# Sheet1.net
KiCad netlist of a schematic drawn in Altium Designer
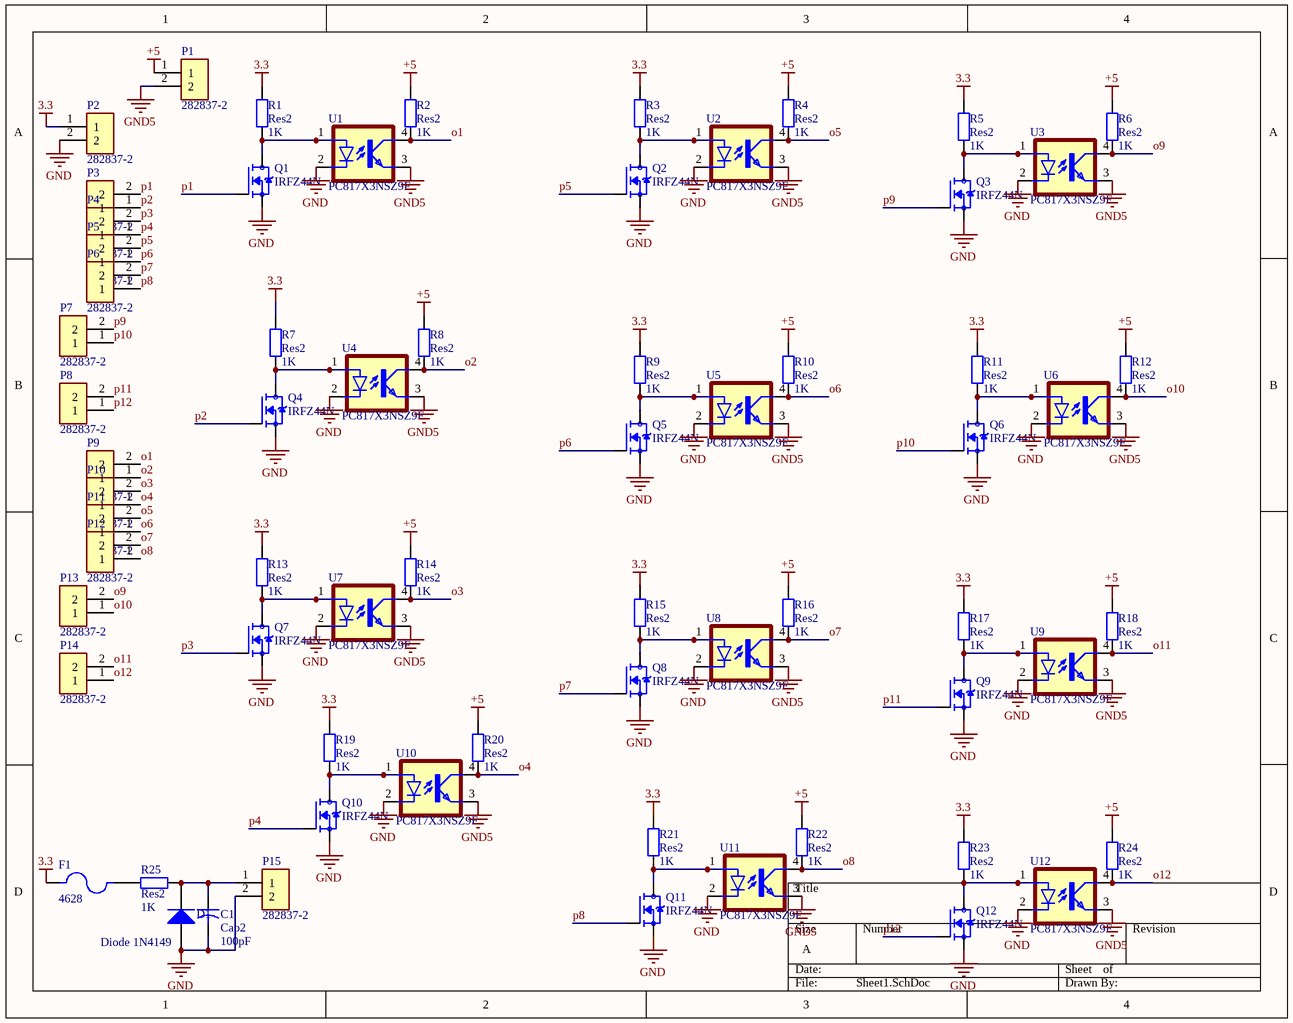
[diagram p0: Sheet1.SchDoc]

(export (version "E")
  (design (tool "Eeschema 10.0.6"))
  (components
    (comp (ref "C1")
      (value "Cap2")
      (footprint "CAPR5-4X5")
      (description "Capacitor")
      (fields (field (name "ALTIUM_VALUE") "100pF") (field (name "PUBLISHER") "Altium Limited"))
      (libsource (lib "Miscellaneous Devices") (part "Cap2"))
    )
    (comp (ref "D1")
      (value "Diode 1N4149")
      (footprint "DO-35A")
      (description "Computer Diode")
      (fields (field (name "PUBLISHER") "Altium Limited"))
      (libsource (lib "Miscellaneous Devices") (part "Diode 1N4149"))
    )
    (comp (ref "F1")
      (value "4628")
      (footprint "FUSE_4628")
      (description "5mm Slim Line Fuse holder")
      (fields (field (name "MF") "Keystone"))
      (libsource (lib "4628") (part "4628"))
    )
    (comp (ref "P1")
      (value "282837-2")
      (footprint "TE_282837-2")
      (fields (field (name "MF") "TE Connectivity"))
      (libsource (lib "") (part "282837-2_1"))
    )
    (comp (ref "P2")
      (value "282837-2")
      (footprint "TE_282837-2")
      (fields (field (name "MF") "TE Connectivity"))
      (libsource (lib "") (part "282837-2_1"))
    )
    (comp (ref "P3")
      (value "282837-2")
      (footprint "TE_282837-2")
      (fields (field (name "MF") "TE Connectivity"))
      (libsource (lib "282837-2") (part "282837-2"))
    )
    (comp (ref "P4")
      (value "282837-2")
      (footprint "TE_282837-2")
      (fields (field (name "MF") "TE Connectivity"))
      (libsource (lib "282837-2") (part "282837-2"))
    )
    (comp (ref "P5")
      (value "282837-2")
      (footprint "TE_282837-2")
      (fields (field (name "MF") "TE Connectivity"))
      (libsource (lib "282837-2") (part "282837-2"))
    )
    (comp (ref "P6")
      (value "282837-2")
      (footprint "TE_282837-2")
      (fields (field (name "MF") "TE Connectivity"))
      (libsource (lib "282837-2") (part "282837-2"))
    )
    (comp (ref "P7")
      (value "282837-2")
      (footprint "TE_282837-2")
      (fields (field (name "MF") "TE Connectivity"))
      (libsource (lib "282837-2") (part "282837-2"))
    )
    (comp (ref "P8")
      (value "282837-2")
      (footprint "TE_282837-2")
      (fields (field (name "MF") "TE Connectivity"))
      (libsource (lib "282837-2") (part "282837-2"))
    )
    (comp (ref "P9")
      (value "282837-2")
      (footprint "TE_282837-2")
      (fields (field (name "MF") "TE Connectivity"))
      (libsource (lib "282837-2") (part "282837-2"))
    )
    (comp (ref "P10")
      (value "282837-2")
      (footprint "TE_282837-2")
      (fields (field (name "MF") "TE Connectivity"))
      (libsource (lib "282837-2") (part "282837-2"))
    )
    (comp (ref "P11")
      (value "282837-2")
      (footprint "TE_282837-2")
      (fields (field (name "MF") "TE Connectivity"))
      (libsource (lib "282837-2") (part "282837-2"))
    )
    (comp (ref "P12")
      (value "282837-2")
      (footprint "TE_282837-2")
      (fields (field (name "MF") "TE Connectivity"))
      (libsource (lib "282837-2") (part "282837-2"))
    )
    (comp (ref "P13")
      (value "282837-2")
      (footprint "TE_282837-2")
      (fields (field (name "MF") "TE Connectivity"))
      (libsource (lib "282837-2") (part "282837-2"))
    )
    (comp (ref "P14")
      (value "282837-2")
      (footprint "TE_282837-2")
      (fields (field (name "MF") "TE Connectivity"))
      (libsource (lib "282837-2") (part "282837-2"))
    )
    (comp (ref "P15")
      (value "282837-2")
      (footprint "TE_282837-2")
      (fields (field (name "MF") "TE Connectivity"))
      (libsource (lib "") (part "282837-2_1"))
    )
    (comp (ref "Q1")
      (value "IRFZ44N")
      (footprint "TO254P1016X419X2286-3")
      (description "N-Channel 55 V 49A (Tc) 94W (Tc) Through Hole TO-220AB")
      (fields (field (name "MF") "Infineon Technologies"))
      (libsource (lib "IRFZ44N") (part "IRFZ44N"))
    )
    (comp (ref "Q2")
      (value "IRFZ44N")
      (footprint "TO254P1016X419X2286-3")
      (description "N-Channel 55 V 49A (Tc) 94W (Tc) Through Hole TO-220AB")
      (fields (field (name "MF") "Infineon Technologies"))
      (libsource (lib "IRFZ44N") (part "IRFZ44N"))
    )
    (comp (ref "Q3")
      (value "IRFZ44N")
      (footprint "TO254P1016X419X2286-3")
      (description "N-Channel 55 V 49A (Tc) 94W (Tc) Through Hole TO-220AB")
      (fields (field (name "MF") "Infineon Technologies"))
      (libsource (lib "IRFZ44N") (part "IRFZ44N"))
    )
    (comp (ref "Q4")
      (value "IRFZ44N")
      (footprint "TO254P1016X419X2286-3")
      (description "N-Channel 55 V 49A (Tc) 94W (Tc) Through Hole TO-220AB")
      (fields (field (name "MF") "Infineon Technologies"))
      (libsource (lib "IRFZ44N") (part "IRFZ44N"))
    )
    (comp (ref "Q5")
      (value "IRFZ44N")
      (footprint "TO254P1016X419X2286-3")
      (description "N-Channel 55 V 49A (Tc) 94W (Tc) Through Hole TO-220AB")
      (fields (field (name "MF") "Infineon Technologies"))
      (libsource (lib "IRFZ44N") (part "IRFZ44N"))
    )
    (comp (ref "Q6")
      (value "IRFZ44N")
      (footprint "TO254P1016X419X2286-3")
      (description "N-Channel 55 V 49A (Tc) 94W (Tc) Through Hole TO-220AB")
      (fields (field (name "MF") "Infineon Technologies"))
      (libsource (lib "IRFZ44N") (part "IRFZ44N"))
    )
    (comp (ref "Q7")
      (value "IRFZ44N")
      (footprint "TO254P1016X419X2286-3")
      (description "N-Channel 55 V 49A (Tc) 94W (Tc) Through Hole TO-220AB")
      (fields (field (name "MF") "Infineon Technologies"))
      (libsource (lib "IRFZ44N") (part "IRFZ44N"))
    )
    (comp (ref "Q8")
      (value "IRFZ44N")
      (footprint "TO254P1016X419X2286-3")
      (description "N-Channel 55 V 49A (Tc) 94W (Tc) Through Hole TO-220AB")
      (fields (field (name "MF") "Infineon Technologies"))
      (libsource (lib "IRFZ44N") (part "IRFZ44N"))
    )
    (comp (ref "Q9")
      (value "IRFZ44N")
      (footprint "TO254P1016X419X2286-3")
      (description "N-Channel 55 V 49A (Tc) 94W (Tc) Through Hole TO-220AB")
      (fields (field (name "MF") "Infineon Technologies"))
      (libsource (lib "IRFZ44N") (part "IRFZ44N"))
    )
    (comp (ref "Q10")
      (value "IRFZ44N")
      (footprint "TO254P1016X419X2286-3")
      (description "N-Channel 55 V 49A (Tc) 94W (Tc) Through Hole TO-220AB")
      (fields (field (name "MF") "Infineon Technologies"))
      (libsource (lib "IRFZ44N") (part "IRFZ44N"))
    )
    (comp (ref "Q11")
      (value "IRFZ44N")
      (footprint "TO254P1016X419X2286-3")
      (description "N-Channel 55 V 49A (Tc) 94W (Tc) Through Hole TO-220AB")
      (fields (field (name "MF") "Infineon Technologies"))
      (libsource (lib "IRFZ44N") (part "IRFZ44N"))
    )
    (comp (ref "Q12")
      (value "IRFZ44N")
      (footprint "TO254P1016X419X2286-3")
      (description "N-Channel 55 V 49A (Tc) 94W (Tc) Through Hole TO-220AB")
      (fields (field (name "MF") "Infineon Technologies"))
      (libsource (lib "IRFZ44N") (part "IRFZ44N"))
    )
    (comp (ref "R1")
      (value "Res2")
      (footprint "AXIAL-0.4")
      (description "Resistor")
      (fields (field (name "ALTIUM_VALUE") "1K") (field (name "PUBLISHER") "Altium Limited"))
      (libsource (lib "Miscellaneous Devices") (part "Res2"))
    )
    (comp (ref "R2")
      (value "Res2")
      (footprint "AXIAL-0.4")
      (description "Resistor")
      (fields (field (name "ALTIUM_VALUE") "1K") (field (name "PUBLISHER") "Altium Limited"))
      (libsource (lib "Miscellaneous Devices") (part "Res2"))
    )
    (comp (ref "R3")
      (value "Res2")
      (footprint "AXIAL-0.4")
      (description "Resistor")
      (fields (field (name "ALTIUM_VALUE") "1K") (field (name "PUBLISHER") "Altium Limited"))
      (libsource (lib "Miscellaneous Devices") (part "Res2"))
    )
    (comp (ref "R4")
      (value "Res2")
      (footprint "AXIAL-0.4")
      (description "Resistor")
      (fields (field (name "ALTIUM_VALUE") "1K") (field (name "PUBLISHER") "Altium Limited"))
      (libsource (lib "Miscellaneous Devices") (part "Res2"))
    )
    (comp (ref "R5")
      (value "Res2")
      (footprint "AXIAL-0.4")
      (description "Resistor")
      (fields (field (name "ALTIUM_VALUE") "1K") (field (name "PUBLISHER") "Altium Limited"))
      (libsource (lib "Miscellaneous Devices") (part "Res2"))
    )
    (comp (ref "R6")
      (value "Res2")
      (footprint "AXIAL-0.4")
      (description "Resistor")
      (fields (field (name "ALTIUM_VALUE") "1K") (field (name "PUBLISHER") "Altium Limited"))
      (libsource (lib "Miscellaneous Devices") (part "Res2"))
    )
    (comp (ref "R7")
      (value "Res2")
      (footprint "AXIAL-0.4")
      (description "Resistor")
      (fields (field (name "ALTIUM_VALUE") "1K") (field (name "PUBLISHER") "Altium Limited"))
      (libsource (lib "Miscellaneous Devices") (part "Res2"))
    )
    (comp (ref "R8")
      (value "Res2")
      (footprint "AXIAL-0.4")
      (description "Resistor")
      (fields (field (name "ALTIUM_VALUE") "1K") (field (name "PUBLISHER") "Altium Limited"))
      (libsource (lib "Miscellaneous Devices") (part "Res2"))
    )
    (comp (ref "R9")
      (value "Res2")
      (footprint "AXIAL-0.4")
      (description "Resistor")
      (fields (field (name "ALTIUM_VALUE") "1K") (field (name "PUBLISHER") "Altium Limited"))
      (libsource (lib "Miscellaneous Devices") (part "Res2"))
    )
    (comp (ref "R10")
      (value "Res2")
      (footprint "AXIAL-0.4")
      (description "Resistor")
      (fields (field (name "ALTIUM_VALUE") "1K") (field (name "PUBLISHER") "Altium Limited"))
      (libsource (lib "Miscellaneous Devices") (part "Res2"))
    )
    (comp (ref "R11")
      (value "Res2")
      (footprint "AXIAL-0.4")
      (description "Resistor")
      (fields (field (name "ALTIUM_VALUE") "1K") (field (name "PUBLISHER") "Altium Limited"))
      (libsource (lib "Miscellaneous Devices") (part "Res2"))
    )
    (comp (ref "R12")
      (value "Res2")
      (footprint "AXIAL-0.4")
      (description "Resistor")
      (fields (field (name "ALTIUM_VALUE") "1K") (field (name "PUBLISHER") "Altium Limited"))
      (libsource (lib "Miscellaneous Devices") (part "Res2"))
    )
    (comp (ref "R13")
      (value "Res2")
      (footprint "AXIAL-0.4")
      (description "Resistor")
      (fields (field (name "ALTIUM_VALUE") "1K") (field (name "PUBLISHER") "Altium Limited"))
      (libsource (lib "Miscellaneous Devices") (part "Res2"))
    )
    (comp (ref "R14")
      (value "Res2")
      (footprint "AXIAL-0.4")
      (description "Resistor")
      (fields (field (name "ALTIUM_VALUE") "1K") (field (name "PUBLISHER") "Altium Limited"))
      (libsource (lib "Miscellaneous Devices") (part "Res2"))
    )
    (comp (ref "R15")
      (value "Res2")
      (footprint "AXIAL-0.4")
      (description "Resistor")
      (fields (field (name "ALTIUM_VALUE") "1K") (field (name "PUBLISHER") "Altium Limited"))
      (libsource (lib "Miscellaneous Devices") (part "Res2"))
    )
    (comp (ref "R16")
      (value "Res2")
      (footprint "AXIAL-0.4")
      (description "Resistor")
      (fields (field (name "ALTIUM_VALUE") "1K") (field (name "PUBLISHER") "Altium Limited"))
      (libsource (lib "Miscellaneous Devices") (part "Res2"))
    )
    (comp (ref "R17")
      (value "Res2")
      (footprint "AXIAL-0.4")
      (description "Resistor")
      (fields (field (name "ALTIUM_VALUE") "1K") (field (name "PUBLISHER") "Altium Limited"))
      (libsource (lib "Miscellaneous Devices") (part "Res2"))
    )
    (comp (ref "R18")
      (value "Res2")
      (footprint "AXIAL-0.4")
      (description "Resistor")
      (fields (field (name "ALTIUM_VALUE") "1K") (field (name "PUBLISHER") "Altium Limited"))
      (libsource (lib "Miscellaneous Devices") (part "Res2"))
    )
    (comp (ref "R19")
      (value "Res2")
      (footprint "AXIAL-0.4")
      (description "Resistor")
      (fields (field (name "ALTIUM_VALUE") "1K") (field (name "PUBLISHER") "Altium Limited"))
      (libsource (lib "Miscellaneous Devices") (part "Res2"))
    )
    (comp (ref "R20")
      (value "Res2")
      (footprint "AXIAL-0.4")
      (description "Resistor")
      (fields (field (name "ALTIUM_VALUE") "1K") (field (name "PUBLISHER") "Altium Limited"))
      (libsource (lib "Miscellaneous Devices") (part "Res2"))
    )
    (comp (ref "R21")
      (value "Res2")
      (footprint "AXIAL-0.4")
      (description "Resistor")
      (fields (field (name "ALTIUM_VALUE") "1K") (field (name "PUBLISHER") "Altium Limited"))
      (libsource (lib "Miscellaneous Devices") (part "Res2"))
    )
    (comp (ref "R22")
      (value "Res2")
      (footprint "AXIAL-0.4")
      (description "Resistor")
      (fields (field (name "ALTIUM_VALUE") "1K") (field (name "PUBLISHER") "Altium Limited"))
      (libsource (lib "Miscellaneous Devices") (part "Res2"))
    )
    (comp (ref "R23")
      (value "Res2")
      (footprint "AXIAL-0.4")
      (description "Resistor")
      (fields (field (name "ALTIUM_VALUE") "1K") (field (name "PUBLISHER") "Altium Limited"))
      (libsource (lib "Miscellaneous Devices") (part "Res2"))
    )
    (comp (ref "R24")
      (value "Res2")
      (footprint "AXIAL-0.4")
      (description "Resistor")
      (fields (field (name "ALTIUM_VALUE") "1K") (field (name "PUBLISHER") "Altium Limited"))
      (libsource (lib "Miscellaneous Devices") (part "Res2"))
    )
    (comp (ref "R25")
      (value "Res2")
      (footprint "AXIAL-0.4")
      (description "Resistor")
      (fields (field (name "ALTIUM_VALUE") "1K") (field (name "PUBLISHER") "Altium Limited"))
      (libsource (lib "") (part "Res2_1"))
    )
    (comp (ref "U1")
      (value "PC817X3NSZ9F")
      (footprint "DIL04")
      (description "Optoisolator Transistor Output 5000Vrms 1 Channel 4-DIP")
      (fields (field (name "MF") "Sharp Microelectronics"))
      (libsource (lib "PC817X3NSZ9F") (part "PC817X3NSZ9F"))
    )
    (comp (ref "U2")
      (value "PC817X3NSZ9F")
      (footprint "DIL04")
      (description "Optoisolator Transistor Output 5000Vrms 1 Channel 4-DIP")
      (fields (field (name "MF") "Sharp Microelectronics"))
      (libsource (lib "PC817X3NSZ9F") (part "PC817X3NSZ9F"))
    )
    (comp (ref "U3")
      (value "PC817X3NSZ9F")
      (footprint "DIL04")
      (description "Optoisolator Transistor Output 5000Vrms 1 Channel 4-DIP")
      (fields (field (name "MF") "Sharp Microelectronics"))
      (libsource (lib "PC817X3NSZ9F") (part "PC817X3NSZ9F"))
    )
    (comp (ref "U4")
      (value "PC817X3NSZ9F")
      (footprint "DIL04")
      (description "Optoisolator Transistor Output 5000Vrms 1 Channel 4-DIP")
      (fields (field (name "MF") "Sharp Microelectronics"))
      (libsource (lib "PC817X3NSZ9F") (part "PC817X3NSZ9F"))
    )
    (comp (ref "U5")
      (value "PC817X3NSZ9F")
      (footprint "DIL04")
      (description "Optoisolator Transistor Output 5000Vrms 1 Channel 4-DIP")
      (fields (field (name "MF") "Sharp Microelectronics"))
      (libsource (lib "PC817X3NSZ9F") (part "PC817X3NSZ9F"))
    )
    (comp (ref "U6")
      (value "PC817X3NSZ9F")
      (footprint "DIL04")
      (description "Optoisolator Transistor Output 5000Vrms 1 Channel 4-DIP")
      (fields (field (name "MF") "Sharp Microelectronics"))
      (libsource (lib "PC817X3NSZ9F") (part "PC817X3NSZ9F"))
    )
    (comp (ref "U7")
      (value "PC817X3NSZ9F")
      (footprint "DIL04")
      (description "Optoisolator Transistor Output 5000Vrms 1 Channel 4-DIP")
      (fields (field (name "MF") "Sharp Microelectronics"))
      (libsource (lib "PC817X3NSZ9F") (part "PC817X3NSZ9F"))
    )
    (comp (ref "U8")
      (value "PC817X3NSZ9F")
      (footprint "DIL04")
      (description "Optoisolator Transistor Output 5000Vrms 1 Channel 4-DIP")
      (fields (field (name "MF") "Sharp Microelectronics"))
      (libsource (lib "PC817X3NSZ9F") (part "PC817X3NSZ9F"))
    )
    (comp (ref "U9")
      (value "PC817X3NSZ9F")
      (footprint "DIL04")
      (description "Optoisolator Transistor Output 5000Vrms 1 Channel 4-DIP")
      (fields (field (name "MF") "Sharp Microelectronics"))
      (libsource (lib "PC817X3NSZ9F") (part "PC817X3NSZ9F"))
    )
    (comp (ref "U10")
      (value "PC817X3NSZ9F")
      (footprint "DIL04")
      (description "Optoisolator Transistor Output 5000Vrms 1 Channel 4-DIP")
      (fields (field (name "MF") "Sharp Microelectronics"))
      (libsource (lib "PC817X3NSZ9F") (part "PC817X3NSZ9F"))
    )
    (comp (ref "U11")
      (value "PC817X3NSZ9F")
      (footprint "DIL04")
      (description "Optoisolator Transistor Output 5000Vrms 1 Channel 4-DIP")
      (fields (field (name "MF") "Sharp Microelectronics"))
      (libsource (lib "PC817X3NSZ9F") (part "PC817X3NSZ9F"))
    )
    (comp (ref "U12")
      (value "PC817X3NSZ9F")
      (footprint "DIL04")
      (description "Optoisolator Transistor Output 5000Vrms 1 Channel 4-DIP")
      (fields (field (name "MF") "Sharp Microelectronics"))
      (libsource (lib "PC817X3NSZ9F") (part "PC817X3NSZ9F"))
    )
  )
  (nets
    (net (code "1") (name "+5") (class "Default")
      (node (ref "P1") (pin "1") (pinfunction "1_1") (pintype "passive"))
      (node (ref "R10") (pin "2") (pinfunction "2_2") (pintype "passive"))
      (node (ref "R12") (pin "2") (pinfunction "2_2") (pintype "passive"))
      (node (ref "R14") (pin "2") (pinfunction "2_2") (pintype "passive"))
      (node (ref "R16") (pin "2") (pinfunction "2_2") (pintype "passive"))
      (node (ref "R18") (pin "2") (pinfunction "2_2") (pintype "passive"))
      (node (ref "R2") (pin "2") (pinfunction "2_2") (pintype "passive"))
      (node (ref "R20") (pin "2") (pinfunction "2_2") (pintype "passive"))
      (node (ref "R22") (pin "2") (pinfunction "2_2") (pintype "passive"))
      (node (ref "R24") (pin "2") (pinfunction "2_2") (pintype "passive"))
      (node (ref "R4") (pin "2") (pinfunction "2_2") (pintype "passive"))
      (node (ref "R6") (pin "2") (pinfunction "2_2") (pintype "passive"))
      (node (ref "R8") (pin "2") (pinfunction "2_2") (pintype "passive"))
    )
    (net (code "2") (name "/o1") (class "Default")
      (node (ref "P9") (pin "2") (pinfunction "2_2") (pintype "passive"))
      (node (ref "R2") (pin "1") (pinfunction "1_1") (pintype "passive"))
      (node (ref "U1") (pin "4") (pinfunction "COL_4") (pintype "passive"))
    )
    (net (code "3") (name "/o2") (class "Default")
      (node (ref "P9") (pin "1") (pinfunction "1_1") (pintype "passive"))
      (node (ref "R8") (pin "1") (pinfunction "1_1") (pintype "passive"))
      (node (ref "U4") (pin "4") (pinfunction "COL_4") (pintype "passive"))
    )
    (net (code "4") (name "/o3") (class "Default")
      (node (ref "P10") (pin "2") (pinfunction "2_2") (pintype "passive"))
      (node (ref "R14") (pin "1") (pinfunction "1_1") (pintype "passive"))
      (node (ref "U7") (pin "4") (pinfunction "COL_4") (pintype "passive"))
    )
    (net (code "5") (name "/o4") (class "Default")
      (node (ref "P10") (pin "1") (pinfunction "1_1") (pintype "passive"))
      (node (ref "R20") (pin "1") (pinfunction "1_1") (pintype "passive"))
      (node (ref "U10") (pin "4") (pinfunction "COL_4") (pintype "passive"))
    )
    (net (code "6") (name "/o5") (class "Default")
      (node (ref "P11") (pin "2") (pinfunction "2_2") (pintype "passive"))
      (node (ref "R4") (pin "1") (pinfunction "1_1") (pintype "passive"))
      (node (ref "U2") (pin "4") (pinfunction "COL_4") (pintype "passive"))
    )
    (net (code "7") (name "/o6") (class "Default")
      (node (ref "P11") (pin "1") (pinfunction "1_1") (pintype "passive"))
      (node (ref "R10") (pin "1") (pinfunction "1_1") (pintype "passive"))
      (node (ref "U5") (pin "4") (pinfunction "COL_4") (pintype "passive"))
    )
    (net (code "8") (name "/o7") (class "Default")
      (node (ref "P12") (pin "2") (pinfunction "2_2") (pintype "passive"))
      (node (ref "R16") (pin "1") (pinfunction "1_1") (pintype "passive"))
      (node (ref "U8") (pin "4") (pinfunction "COL_4") (pintype "passive"))
    )
    (net (code "9") (name "/o8") (class "Default")
      (node (ref "P12") (pin "1") (pinfunction "1_1") (pintype "passive"))
      (node (ref "R22") (pin "1") (pinfunction "1_1") (pintype "passive"))
      (node (ref "U11") (pin "4") (pinfunction "COL_4") (pintype "passive"))
    )
    (net (code "10") (name "/o9") (class "Default")
      (node (ref "P13") (pin "2") (pinfunction "2_2") (pintype "passive"))
      (node (ref "R6") (pin "1") (pinfunction "1_1") (pintype "passive"))
      (node (ref "U3") (pin "4") (pinfunction "COL_4") (pintype "passive"))
    )
    (net (code "11") (name "/o10") (class "Default")
      (node (ref "P13") (pin "1") (pinfunction "1_1") (pintype "passive"))
      (node (ref "R12") (pin "1") (pinfunction "1_1") (pintype "passive"))
      (node (ref "U6") (pin "4") (pinfunction "COL_4") (pintype "passive"))
    )
    (net (code "12") (name "/o11") (class "Default")
      (node (ref "P14") (pin "2") (pinfunction "2_2") (pintype "passive"))
      (node (ref "R18") (pin "1") (pinfunction "1_1") (pintype "passive"))
      (node (ref "U9") (pin "4") (pinfunction "COL_4") (pintype "passive"))
    )
    (net (code "13") (name "/o12") (class "Default")
      (node (ref "P14") (pin "1") (pinfunction "1_1") (pintype "passive"))
      (node (ref "R24") (pin "1") (pinfunction "1_1") (pintype "passive"))
      (node (ref "U12") (pin "4") (pinfunction "COL_4") (pintype "passive"))
    )
    (net (code "14") (name "/p1") (class "Default")
      (node (ref "P3") (pin "2") (pinfunction "2_2") (pintype "passive"))
      (node (ref "Q1") (pin "1") (pinfunction "G_1") (pintype "passive"))
    )
    (net (code "15") (name "/p2") (class "Default")
      (node (ref "P3") (pin "1") (pinfunction "1_1") (pintype "passive"))
      (node (ref "Q4") (pin "1") (pinfunction "G_1") (pintype "passive"))
    )
    (net (code "16") (name "/p3") (class "Default")
      (node (ref "P4") (pin "2") (pinfunction "2_2") (pintype "passive"))
      (node (ref "Q7") (pin "1") (pinfunction "G_1") (pintype "passive"))
    )
    (net (code "17") (name "/p4") (class "Default")
      (node (ref "P4") (pin "1") (pinfunction "1_1") (pintype "passive"))
      (node (ref "Q10") (pin "1") (pinfunction "G_1") (pintype "passive"))
    )
    (net (code "18") (name "/p5") (class "Default")
      (node (ref "P5") (pin "2") (pinfunction "2_2") (pintype "passive"))
      (node (ref "Q2") (pin "1") (pinfunction "G_1") (pintype "passive"))
    )
    (net (code "19") (name "/p6") (class "Default")
      (node (ref "P5") (pin "1") (pinfunction "1_1") (pintype "passive"))
      (node (ref "Q5") (pin "1") (pinfunction "G_1") (pintype "passive"))
    )
    (net (code "20") (name "/p7") (class "Default")
      (node (ref "P6") (pin "2") (pinfunction "2_2") (pintype "passive"))
      (node (ref "Q8") (pin "1") (pinfunction "G_1") (pintype "passive"))
    )
    (net (code "21") (name "/p8") (class "Default")
      (node (ref "P6") (pin "1") (pinfunction "1_1") (pintype "passive"))
      (node (ref "Q11") (pin "1") (pinfunction "G_1") (pintype "passive"))
    )
    (net (code "22") (name "/p9") (class "Default")
      (node (ref "P7") (pin "2") (pinfunction "2_2") (pintype "passive"))
      (node (ref "Q3") (pin "1") (pinfunction "G_1") (pintype "passive"))
    )
    (net (code "23") (name "/p10") (class "Default")
      (node (ref "P7") (pin "1") (pinfunction "1_1") (pintype "passive"))
      (node (ref "Q6") (pin "1") (pinfunction "G_1") (pintype "passive"))
    )
    (net (code "24") (name "/p11") (class "Default")
      (node (ref "P8") (pin "2") (pinfunction "2_2") (pintype "passive"))
      (node (ref "Q9") (pin "1") (pinfunction "G_1") (pintype "passive"))
    )
    (net (code "25") (name "/p12") (class "Default")
      (node (ref "P8") (pin "1") (pinfunction "1_1") (pintype "passive"))
      (node (ref "Q12") (pin "1") (pinfunction "G_1") (pintype "passive"))
    )
    (net (code "26") (name "3.3") (class "Default")
      (node (ref "F1") (pin "1") (pinfunction "1_1") (pintype "passive"))
      (node (ref "P2") (pin "1") (pinfunction "1_1") (pintype "passive"))
      (node (ref "R1") (pin "2") (pinfunction "2_2") (pintype "passive"))
      (node (ref "R11") (pin "2") (pinfunction "2_2") (pintype "passive"))
      (node (ref "R13") (pin "2") (pinfunction "2_2") (pintype "passive"))
      (node (ref "R15") (pin "2") (pinfunction "2_2") (pintype "passive"))
      (node (ref "R17") (pin "2") (pinfunction "2_2") (pintype "passive"))
      (node (ref "R19") (pin "2") (pinfunction "2_2") (pintype "passive"))
      (node (ref "R21") (pin "2") (pinfunction "2_2") (pintype "passive"))
      (node (ref "R23") (pin "2") (pinfunction "2_2") (pintype "passive"))
      (node (ref "R3") (pin "2") (pinfunction "2_2") (pintype "passive"))
      (node (ref "R5") (pin "2") (pinfunction "2_2") (pintype "passive"))
      (node (ref "R7") (pin "2") (pinfunction "2_2") (pintype "passive"))
      (node (ref "R9") (pin "2") (pinfunction "2_2") (pintype "passive"))
    )
    (net (code "27") (name "GND") (class "Default")
      (node (ref "C1") (pin "2") (pinfunction "2_2") (pintype "passive"))
      (node (ref "D1") (pin "1") (pinfunction "A_1") (pintype "passive"))
      (node (ref "P15") (pin "2") (pinfunction "2_2") (pintype "passive"))
      (node (ref "P2") (pin "2") (pinfunction "2_2") (pintype "passive"))
      (node (ref "Q1") (pin "3") (pinfunction "S_3") (pintype "passive"))
      (node (ref "Q10") (pin "3") (pinfunction "S_3") (pintype "passive"))
      (node (ref "Q11") (pin "3") (pinfunction "S_3") (pintype "passive"))
      (node (ref "Q12") (pin "3") (pinfunction "S_3") (pintype "passive"))
      (node (ref "Q2") (pin "3") (pinfunction "S_3") (pintype "passive"))
      (node (ref "Q3") (pin "3") (pinfunction "S_3") (pintype "passive"))
      (node (ref "Q4") (pin "3") (pinfunction "S_3") (pintype "passive"))
      (node (ref "Q5") (pin "3") (pinfunction "S_3") (pintype "passive"))
      (node (ref "Q6") (pin "3") (pinfunction "S_3") (pintype "passive"))
      (node (ref "Q7") (pin "3") (pinfunction "S_3") (pintype "passive"))
      (node (ref "Q8") (pin "3") (pinfunction "S_3") (pintype "passive"))
      (node (ref "Q9") (pin "3") (pinfunction "S_3") (pintype "passive"))
      (node (ref "U1") (pin "2") (pinfunction "C_2") (pintype "passive"))
      (node (ref "U10") (pin "2") (pinfunction "C_2") (pintype "passive"))
      (node (ref "U11") (pin "2") (pinfunction "C_2") (pintype "passive"))
      (node (ref "U12") (pin "2") (pinfunction "C_2") (pintype "passive"))
      (node (ref "U2") (pin "2") (pinfunction "C_2") (pintype "passive"))
      (node (ref "U3") (pin "2") (pinfunction "C_2") (pintype "passive"))
      (node (ref "U4") (pin "2") (pinfunction "C_2") (pintype "passive"))
      (node (ref "U5") (pin "2") (pinfunction "C_2") (pintype "passive"))
      (node (ref "U6") (pin "2") (pinfunction "C_2") (pintype "passive"))
      (node (ref "U7") (pin "2") (pinfunction "C_2") (pintype "passive"))
      (node (ref "U8") (pin "2") (pinfunction "C_2") (pintype "passive"))
      (node (ref "U9") (pin "2") (pinfunction "C_2") (pintype "passive"))
    )
    (net (code "28") (name "GND5") (class "Default")
      (node (ref "P1") (pin "2") (pinfunction "2_2") (pintype "passive"))
      (node (ref "U1") (pin "3") (pinfunction "EMIT_3") (pintype "passive"))
      (node (ref "U10") (pin "3") (pinfunction "EMIT_3") (pintype "passive"))
      (node (ref "U11") (pin "3") (pinfunction "EMIT_3") (pintype "passive"))
      (node (ref "U12") (pin "3") (pinfunction "EMIT_3") (pintype "passive"))
      (node (ref "U2") (pin "3") (pinfunction "EMIT_3") (pintype "passive"))
      (node (ref "U3") (pin "3") (pinfunction "EMIT_3") (pintype "passive"))
      (node (ref "U4") (pin "3") (pinfunction "EMIT_3") (pintype "passive"))
      (node (ref "U5") (pin "3") (pinfunction "EMIT_3") (pintype "passive"))
      (node (ref "U6") (pin "3") (pinfunction "EMIT_3") (pintype "passive"))
      (node (ref "U7") (pin "3") (pinfunction "EMIT_3") (pintype "passive"))
      (node (ref "U8") (pin "3") (pinfunction "EMIT_3") (pintype "passive"))
      (node (ref "U9") (pin "3") (pinfunction "EMIT_3") (pintype "passive"))
    )
    (net (code "29") (name "Net-(D1-K)") (class "Default")
      (node (ref "C1") (pin "1") (pinfunction "1_1") (pintype "passive"))
      (node (ref "D1") (pin "2") (pinfunction "K_2") (pintype "passive"))
      (node (ref "P15") (pin "1") (pinfunction "1_1") (pintype "passive"))
      (node (ref "R25") (pin "1") (pinfunction "1_1") (pintype "passive"))
    )
    (net (code "30") (name "Net-(F1-Pad2)") (class "Default")
      (node (ref "F1") (pin "2") (pinfunction "2_2") (pintype "passive"))
      (node (ref "R25") (pin "2") (pinfunction "2_2") (pintype "passive"))
    )
    (net (code "31") (name "Net-(Q1-D)") (class "Default")
      (node (ref "Q1") (pin "2") (pinfunction "D_2") (pintype "passive"))
      (node (ref "R1") (pin "1") (pinfunction "1_1") (pintype "passive"))
      (node (ref "U1") (pin "1") (pinfunction "A_1") (pintype "passive"))
    )
    (net (code "32") (name "Net-(Q2-D)") (class "Default")
      (node (ref "Q2") (pin "2") (pinfunction "D_2") (pintype "passive"))
      (node (ref "R3") (pin "1") (pinfunction "1_1") (pintype "passive"))
      (node (ref "U2") (pin "1") (pinfunction "A_1") (pintype "passive"))
    )
    (net (code "33") (name "Net-(Q3-D)") (class "Default")
      (node (ref "Q3") (pin "2") (pinfunction "D_2") (pintype "passive"))
      (node (ref "R5") (pin "1") (pinfunction "1_1") (pintype "passive"))
      (node (ref "U3") (pin "1") (pinfunction "A_1") (pintype "passive"))
    )
    (net (code "34") (name "Net-(Q4-D)") (class "Default")
      (node (ref "Q4") (pin "2") (pinfunction "D_2") (pintype "passive"))
      (node (ref "R7") (pin "1") (pinfunction "1_1") (pintype "passive"))
      (node (ref "U4") (pin "1") (pinfunction "A_1") (pintype "passive"))
    )
    (net (code "35") (name "Net-(Q5-D)") (class "Default")
      (node (ref "Q5") (pin "2") (pinfunction "D_2") (pintype "passive"))
      (node (ref "R9") (pin "1") (pinfunction "1_1") (pintype "passive"))
      (node (ref "U5") (pin "1") (pinfunction "A_1") (pintype "passive"))
    )
    (net (code "36") (name "Net-(Q6-D)") (class "Default")
      (node (ref "Q6") (pin "2") (pinfunction "D_2") (pintype "passive"))
      (node (ref "R11") (pin "1") (pinfunction "1_1") (pintype "passive"))
      (node (ref "U6") (pin "1") (pinfunction "A_1") (pintype "passive"))
    )
    (net (code "37") (name "Net-(Q7-D)") (class "Default")
      (node (ref "Q7") (pin "2") (pinfunction "D_2") (pintype "passive"))
      (node (ref "R13") (pin "1") (pinfunction "1_1") (pintype "passive"))
      (node (ref "U7") (pin "1") (pinfunction "A_1") (pintype "passive"))
    )
    (net (code "38") (name "Net-(Q8-D)") (class "Default")
      (node (ref "Q8") (pin "2") (pinfunction "D_2") (pintype "passive"))
      (node (ref "R15") (pin "1") (pinfunction "1_1") (pintype "passive"))
      (node (ref "U8") (pin "1") (pinfunction "A_1") (pintype "passive"))
    )
    (net (code "39") (name "Net-(Q9-D)") (class "Default")
      (node (ref "Q9") (pin "2") (pinfunction "D_2") (pintype "passive"))
      (node (ref "R17") (pin "1") (pinfunction "1_1") (pintype "passive"))
      (node (ref "U9") (pin "1") (pinfunction "A_1") (pintype "passive"))
    )
    (net (code "40") (name "Net-(Q10-D)") (class "Default")
      (node (ref "Q10") (pin "2") (pinfunction "D_2") (pintype "passive"))
      (node (ref "R19") (pin "1") (pinfunction "1_1") (pintype "passive"))
      (node (ref "U10") (pin "1") (pinfunction "A_1") (pintype "passive"))
    )
    (net (code "41") (name "Net-(Q11-D)") (class "Default")
      (node (ref "Q11") (pin "2") (pinfunction "D_2") (pintype "passive"))
      (node (ref "R21") (pin "1") (pinfunction "1_1") (pintype "passive"))
      (node (ref "U11") (pin "1") (pinfunction "A_1") (pintype "passive"))
    )
    (net (code "42") (name "Net-(Q12-D)") (class "Default")
      (node (ref "Q12") (pin "2") (pinfunction "D_2") (pintype "passive"))
      (node (ref "R23") (pin "1") (pinfunction "1_1") (pintype "passive"))
      (node (ref "U12") (pin "1") (pinfunction "A_1") (pintype "passive"))
    )
  )
)
